# jamma-streamer.net
KiCad netlist of a schematic drawn in EAGLE
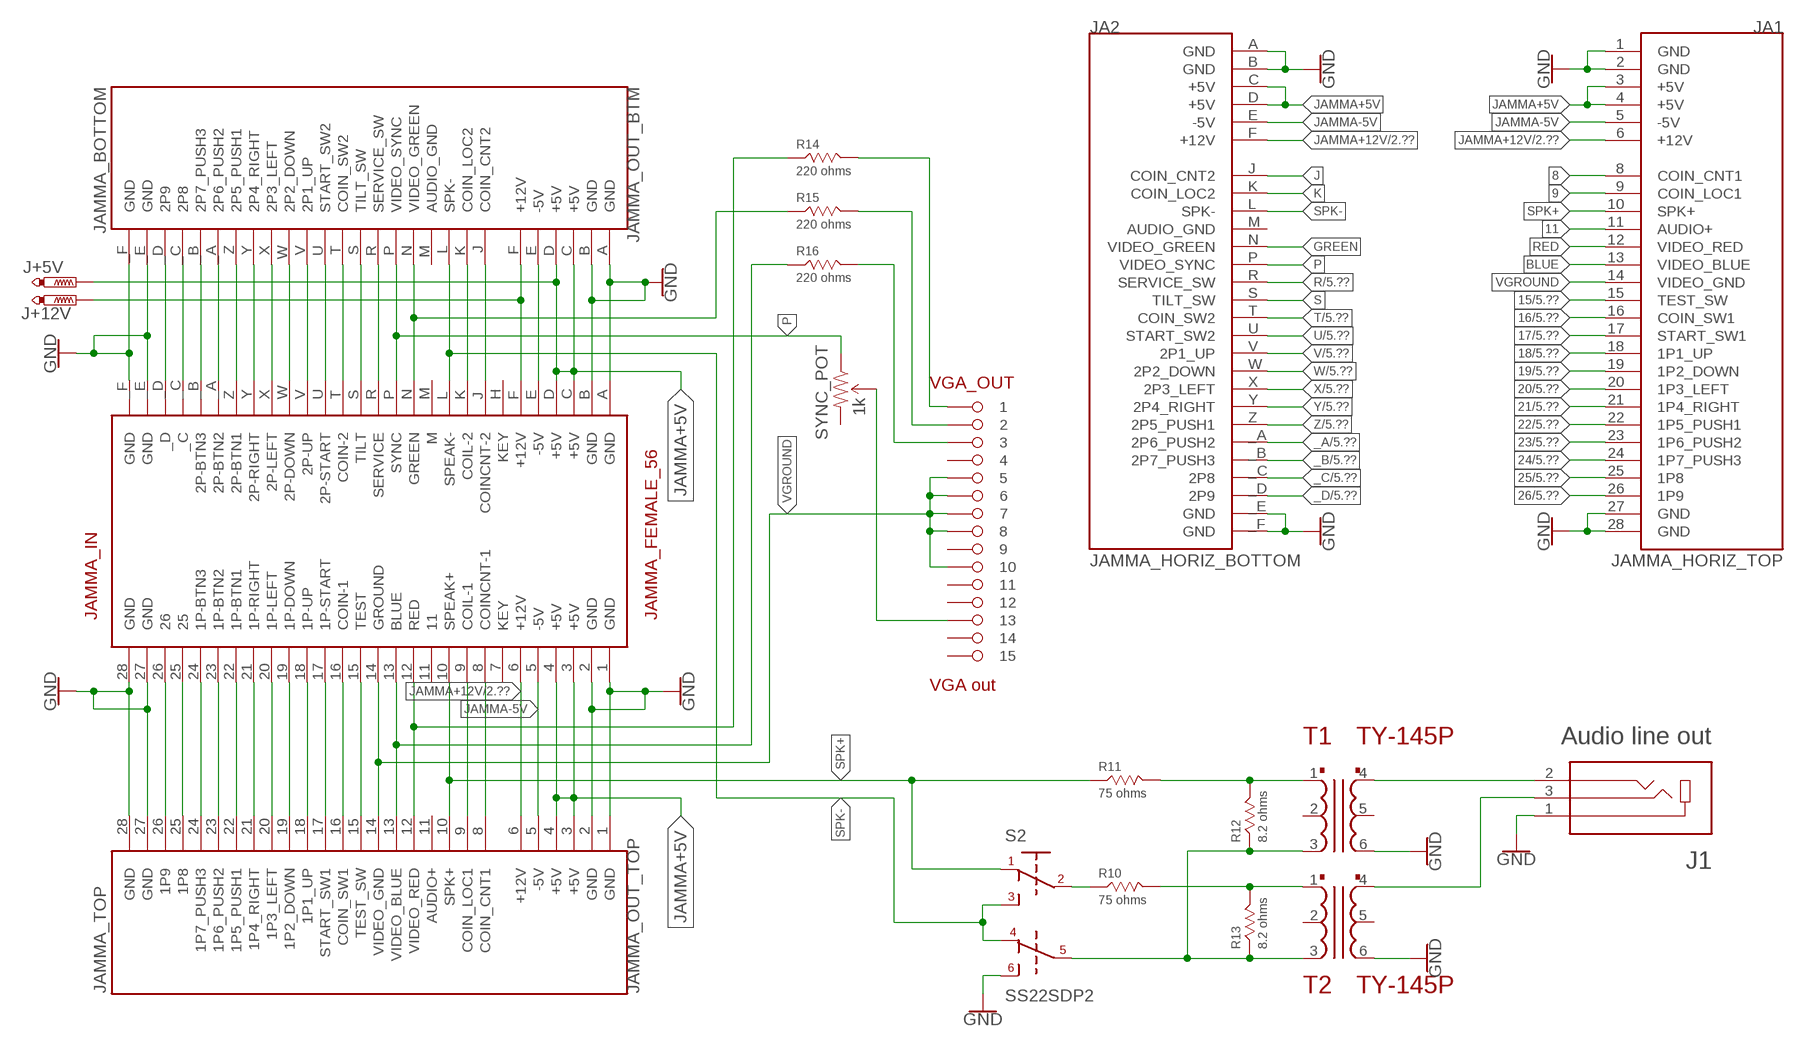
[diagram p0: schematic, sheet 1]
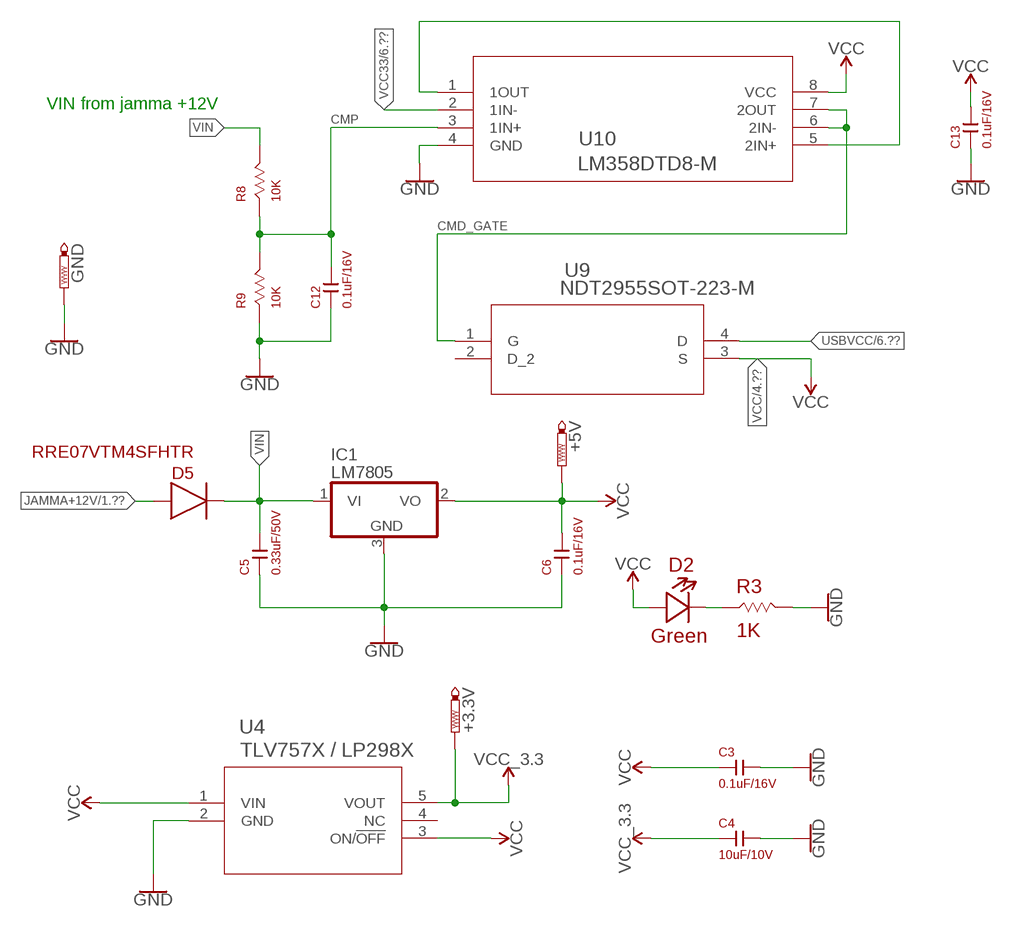
[diagram p1: schematic, sheet 2]
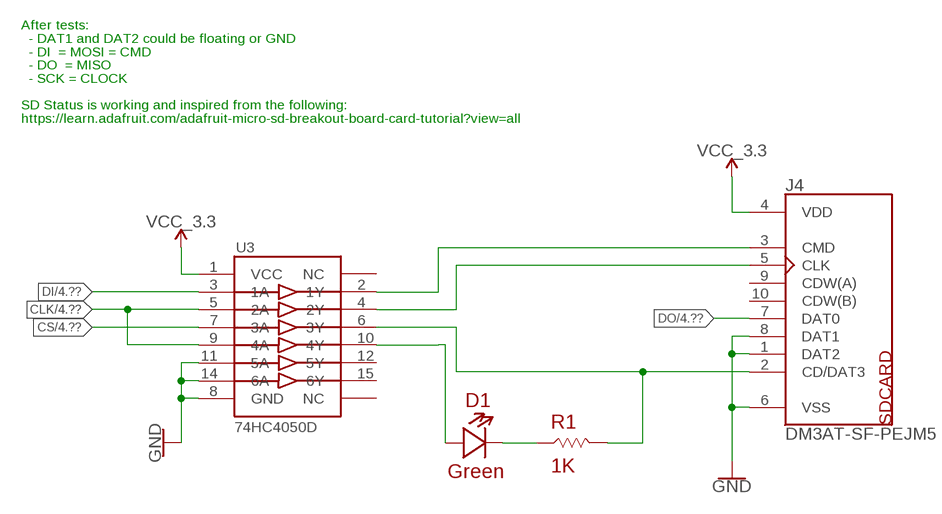
[diagram p2: schematic, sheet 3]
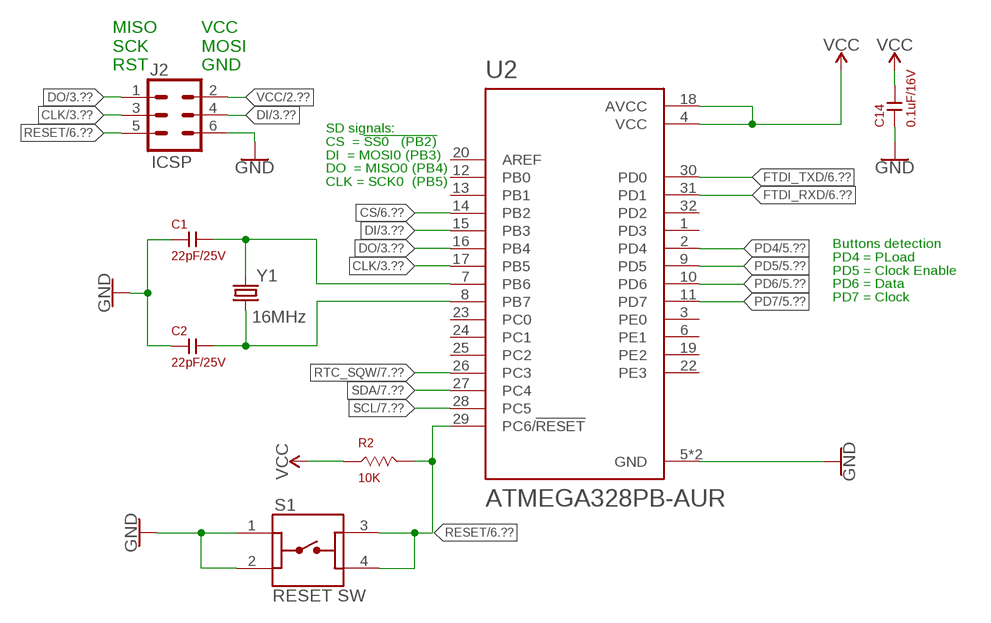
[diagram p3: schematic, sheet 4]
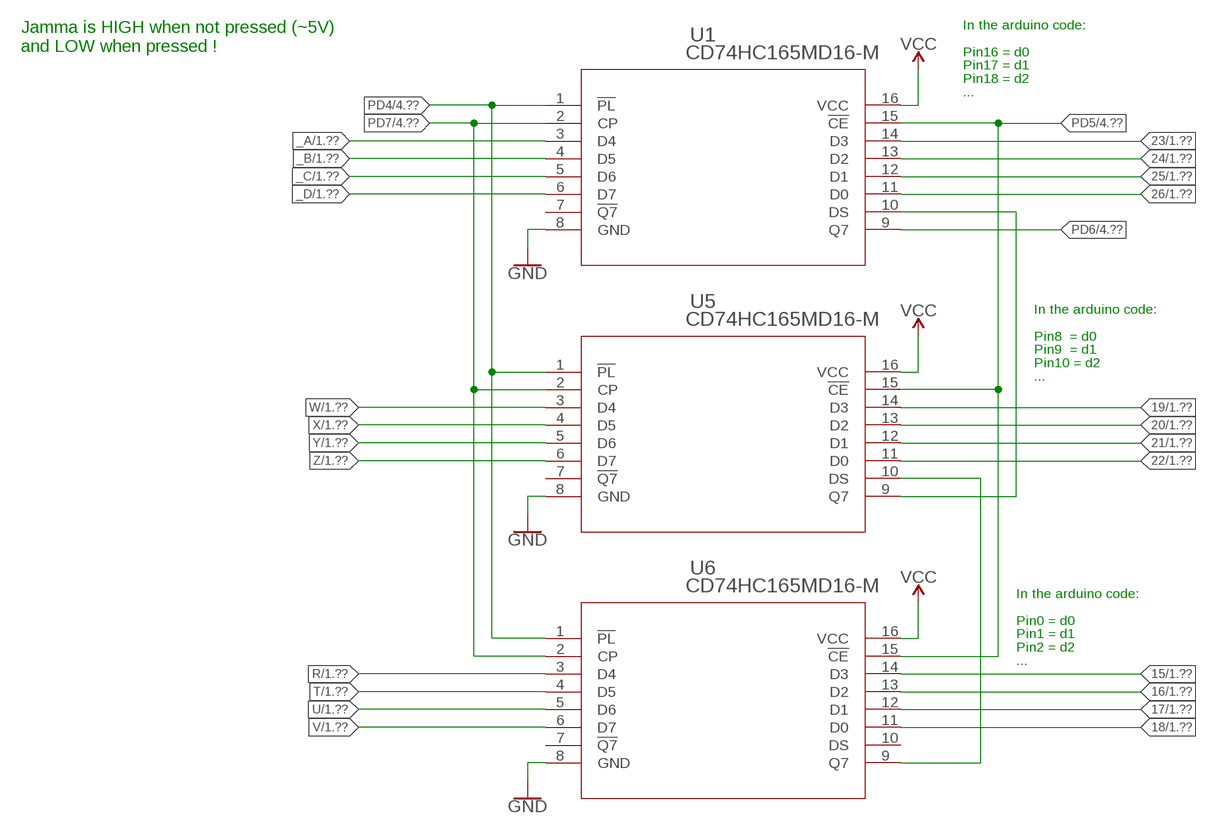
[diagram p4: schematic, sheet 5]
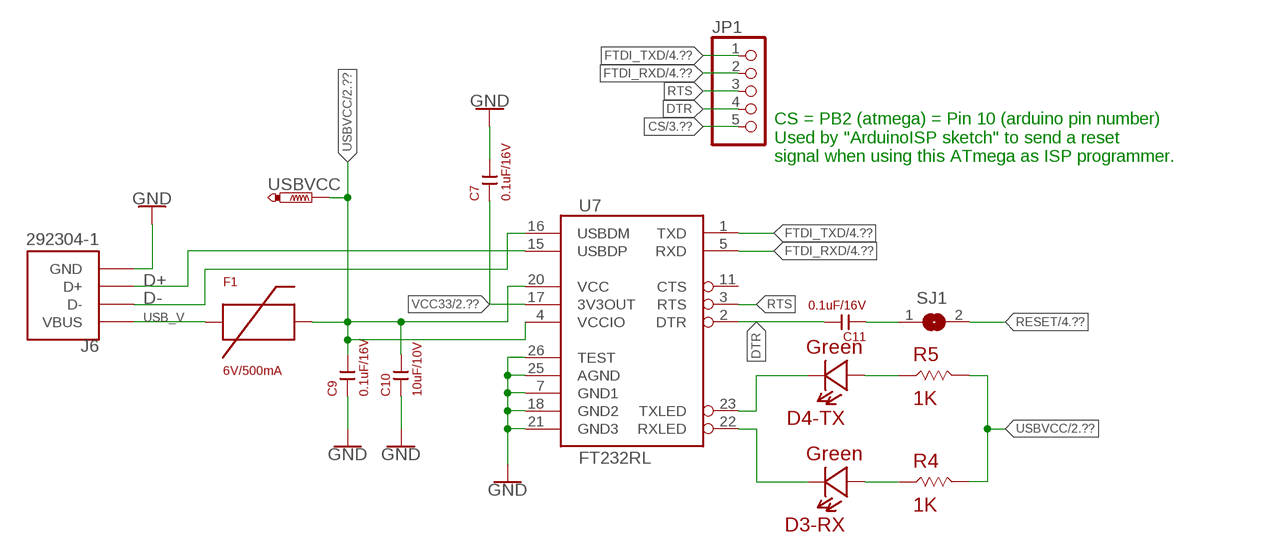
[diagram p5: schematic, sheet 6]
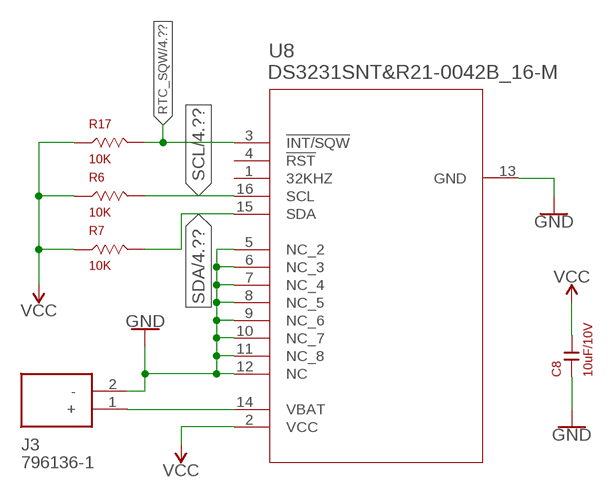
[diagram p6: schematic, sheet 7]

(export (version "E")
  (design (tool "Eeschema 10.0.6"))
  (components
    (comp (ref "U1")
      (value "CD74HC165MD16-M")
      (footprint "eagle-import:D16-M")
      (fields (field (name "MANUFACTURER_PART_NUMBER") "CD74HC165M"))
      (libsource (lib "eagle-import") (part "CD74HC165MD16-M"))
    )
    (comp (ref "U5")
      (value "CD74HC165MD16-M")
      (footprint "eagle-import:D16-M")
      (fields (field (name "MANUFACTURER_PART_NUMBER") "CD74HC165M"))
      (libsource (lib "eagle-import") (part "CD74HC165MD16-M"))
    )
    (comp (ref "U6")
      (value "CD74HC165MD16-M")
      (footprint "eagle-import:D16-M")
      (fields (field (name "MANUFACTURER_PART_NUMBER") "CD74HC165M"))
      (libsource (lib "eagle-import") (part "CD74HC165MD16-M"))
    )
    (comp (ref "D1")
      (value "Green")
      (footprint "eagle-import:604-APTD1608LCGCK")
      (libsource (lib "eagle-import") (part "604-APTD1608LCGCK"))
    )
    (comp (ref "J4")
      (value "DM3AT-SF-PEJM5")
      (footprint "eagle-import:DM3AT-SF-PEJM5_1")
      (fields (field (name "MOUSER_PART_NUMBER") "798-DM3AT-SF-PEJM5"))
      (libsource (lib "eagle-import") (part "DM3AT-SF-PEJM5"))
    )
    (comp (ref "R1")
      (value "1K")
      (footprint "eagle-import:652-CHP0603FX1001ELF")
      (libsource (lib "eagle-import") (part "BOURNS-652CHP0603FX1001ELF"))
    )
    (comp (ref "U3")
      (value "74HC4050D")
      (footprint "eagle-import:SO16")
      (fields (field (name "MF") "Toshiba Semiconductor"))
      (libsource (lib "eagle-import") (part "74HC4050D"))
    )
    (comp (ref "+3.3V")
      (value "PTR1TP15SQ")
      (footprint "eagle-import:TP15SQ")
      (libsource (lib "eagle-import") (part "PTR1TP15SQ"))
    )
    (comp (ref "+5V")
      (value "PTR1TP15SQ")
      (footprint "eagle-import:TP15SQ")
      (libsource (lib "eagle-import") (part "PTR1TP15SQ"))
    )
    (comp (ref "C3")
      (value "0.1uF/16V")
      (footprint "eagle-import:KEMET-C1210C104K4J")
      (libsource (lib "eagle-import") (part "KEMET-C1210C104K4J"))
    )
    (comp (ref "C4")
      (value "10uF/10V")
      (footprint "eagle-import:KEMET-C1210C106K8N")
      (libsource (lib "eagle-import") (part "KEMET-C1210C106K8N"))
    )
    (comp (ref "C5")
      (value "0.33uF/50V")
      (footprint "eagle-import:KEMET-C1206X334K5R")
      (libsource (lib "eagle-import") (part "KEMET-C1206X334K5R"))
    )
    (comp (ref "C6")
      (value "0.1uF/16V")
      (footprint "eagle-import:KEMET-C1210C104K4J")
      (libsource (lib "eagle-import") (part "KEMET-C1210C104K4J"))
    )
    (comp (ref "C12")
      (value "0.1uF/16V")
      (footprint "eagle-import:KEMET-C1210C104K4J")
      (libsource (lib "eagle-import") (part "KEMET-C1210C104K4J"))
    )
    (comp (ref "C13")
      (value "0.1uF/16V")
      (footprint "eagle-import:KEMET-C1210C104K4J")
      (libsource (lib "eagle-import") (part "KEMET-C1210C104K4J"))
    )
    (comp (ref "D2")
      (value "Green")
      (footprint "eagle-import:604-APTD1608LCGCK")
      (libsource (lib "eagle-import") (part "604-APTD1608LCGCK"))
    )
    (comp (ref "D5")
      (value "RRE07VTM4SFHTR")
      (footprint "eagle-import:DIODE-RRE07VTM4SFHTR")
      (libsource (lib "eagle-import") (part "RRE07VTM4SFHTR"))
    )
    (comp (ref "GND")
      (value "PTR1TP15SQ")
      (footprint "eagle-import:TP15SQ")
      (libsource (lib "eagle-import") (part "PTR1TP15SQ"))
    )
    (comp (ref "IC1")
      (value "LM7805")
      (footprint "eagle-import:TO252")
      (libsource (lib "eagle-import") (part "78DT05"))
    )
    (comp (ref "R3")
      (value "1K")
      (footprint "eagle-import:652-CHP0603FX1001ELF")
      (libsource (lib "eagle-import") (part "BOURNS-652CHP0603FX1001ELF"))
    )
    (comp (ref "R8")
      (value "10K")
      (footprint "eagle-import:BOURNS-CRM2512AJW-103ELF")
      (libsource (lib "eagle-import") (part "BOURNS-CRM2512AJW103ELF"))
    )
    (comp (ref "R9")
      (value "10K")
      (footprint "eagle-import:BOURNS-CRM2512AJW-103ELF")
      (libsource (lib "eagle-import") (part "BOURNS-CRM2512AJW103ELF"))
    )
    (comp (ref "U4")
      (value "TLV757X / LP298X")
      (footprint "eagle-import:DBV5-M")
      (fields (field (name "MANUFACTURER_PART_NUMBER") "LP298133DBVR"))
      (libsource (lib "eagle-import") (part "LP2981-33DBVRDBV5-M"))
    )
    (comp (ref "U9")
      (value "NDT2955SOT-223-M")
      (footprint "eagle-import:SOT-223-M")
      (fields (field (name "MANUFACTURER_PART_NUMBER") "NDT2955"))
      (libsource (lib "eagle-import") (part "NDT2955SOT-223-M"))
    )
    (comp (ref "U10")
      (value "LM358DTD8-M")
      (footprint "eagle-import:D8-M")
      (fields (field (name "MANUFACTURER_PART_NUMBER") "LM358DT"))
      (libsource (lib "eagle-import") (part "LM358DTD8-M"))
    )
    (comp (ref "J+5V")
      (value "PTR1TP15SQ")
      (footprint "eagle-import:TP15SQ")
      (libsource (lib "eagle-import") (part "PTR1TP15SQ"))
    )
    (comp (ref "J+12V")
      (value "PTR1TP15SQ")
      (footprint "eagle-import:TP15SQ")
      (libsource (lib "eagle-import") (part "PTR1TP15SQ"))
    )
    (comp (ref "J1")
      (value "Audio line out")
      (footprint "eagle-import:CUI_SJ1-3523N")
      (fields
        (field (name "DIGI-KEY_PART_NUMBER") "CP1-3523N-ND")
        (field (name "MF") "CUI Inc.")
        (field (name "MP") "SJ1-3523N")
        (field (name "SPICEPREFIX") "J")
      )
      (libsource (lib "eagle-import") (part "SJ1-3523N"))
    )
    (comp (ref "JA1")
      (value "JAMMA_HORIZ_TOP")
      (footprint "eagle-import:JAMMA_HORIZ_TOP")
      (libsource (lib "eagle-import") (part "JAMMA_HORIZ_TOP"))
    )
    (comp (ref "JA2")
      (value "JAMMA_HORIZ_BOTTOM")
      (footprint "eagle-import:JAMMA_HORIZ_BOTTOM")
      (libsource (lib "eagle-import") (part "JAMMA_HORIZ_BOTTOM"))
    )
    (comp (ref "JAMMA_IN")
      (value "JAMMA_FEMALE_56")
      (footprint "eagle-import:JAMMA_FEMALE_56")
      (libsource (lib "eagle-import") (part "JAMMA_FEMALE_56"))
    )
    (comp (ref "JAMMA_OUT_BTM")
      (value "JAMMA_BOTTOM")
      (footprint "eagle-import:JAMMA_BOTTOM")
      (libsource (lib "eagle-import") (part "JAMMA_BOTTOM"))
    )
    (comp (ref "JAMMA_OUT_TOP")
      (value "JAMMA_TOP")
      (footprint "eagle-import:JAMMA_TOP")
      (libsource (lib "eagle-import") (part "JAMMA_TOP"))
    )
    (comp (ref "R10")
      (value "75 ohms")
      (footprint "eagle-import:TE_3550_SERIES")
      (fields (field (name "POWER") "5W") (field (name "MOUSER_REF") "279-355075RFT"))
      (libsource (lib "eagle-import") (part "TE3550"))
    )
    (comp (ref "R11")
      (value "75 ohms")
      (footprint "eagle-import:TE_3550_SERIES")
      (fields (field (name "POWER") "5W") (field (name "MOUSER_REF") "279-355075RFT"))
      (libsource (lib "eagle-import") (part "TE3550"))
    )
    (comp (ref "R12")
      (value "8.2 ohms")
      (footprint "eagle-import:TE_3550_SERIES")
      (fields (field (name "POWER") "5W") (field (name "MOUSER_REF") "279-35508R2JT"))
      (libsource (lib "eagle-import") (part "TE3550"))
    )
    (comp (ref "R13")
      (value "8.2 ohms")
      (footprint "eagle-import:TE_3550_SERIES")
      (fields (field (name "POWER") "5W") (field (name "MOUSER_REF") "279-35508R2JT"))
      (libsource (lib "eagle-import") (part "TE3550"))
    )
    (comp (ref "R14")
      (value "220 ohms")
      (footprint "eagle-import:RESC3225X70N")
      (fields
        (field (name "MANUFACTURER_PART_NUMBER") "ERJ-14NF2200U")
        (field (name "MOUSER_PART_NUMBER") "667-ERJ-14NF2200U")
      )
      (libsource (lib "eagle-import") (part "ERJ-14NF2200U"))
    )
    (comp (ref "R15")
      (value "220 ohms")
      (footprint "eagle-import:RESC3225X70N")
      (fields
        (field (name "MANUFACTURER_PART_NUMBER") "ERJ-14NF2200U")
        (field (name "MOUSER_PART_NUMBER") "667-ERJ-14NF2200U")
      )
      (libsource (lib "eagle-import") (part "ERJ-14NF2200U"))
    )
    (comp (ref "R16")
      (value "220 ohms")
      (footprint "eagle-import:RESC3225X70N")
      (fields
        (field (name "MANUFACTURER_PART_NUMBER") "ERJ-14NF2200U")
        (field (name "MOUSER_PART_NUMBER") "667-ERJ-14NF2200U")
      )
      (libsource (lib "eagle-import") (part "ERJ-14NF2200U"))
    )
    (comp (ref "S2")
      (value "SS22SDP2")
      (footprint "eagle-import:SS22SDP2(DPDT)")
      (fields (field (name "MOUSER_PART_NUMBER") "633-SS22SDP2") (field (name "SPICEPREFIX") "X"))
      (libsource (lib "eagle-import") (part "SS22SDP2"))
    )
    (comp (ref "SYNC_POT")
      (value "1k")
      (footprint "eagle-import:TRIM_POT_PTH")
      (libsource (lib "eagle-import") (part "TRIMPOTPTH"))
    )
    (comp (ref "T1")
      (value "TY-145P")
      (footprint "eagle-import:TRIAD-TY-145P")
      (fields (field (name "SPICEPREFIX") "X"))
      (libsource (lib "eagle-import") (part "TRIAD-TY-145P"))
    )
    (comp (ref "T2")
      (value "TY-145P")
      (footprint "eagle-import:TRIAD-TY-145P")
      (fields (field (name "SPICEPREFIX") "X"))
      (libsource (lib "eagle-import") (part "TRIAD-TY-145P"))
    )
    (comp (ref "VGA_OUT")
      (value "VGA out")
      (footprint "eagle-import:HARTING-DSUB-15-FEMALE")
      (libsource (lib "eagle-import") (part "HARTING-DSUB-15-FEMALE"))
    )
    (comp (ref "C7")
      (value "0.1uF/16V")
      (footprint "eagle-import:KEMET-C1210C104K4J")
      (libsource (lib "eagle-import") (part "KEMET-C1210C104K4J"))
    )
    (comp (ref "C9")
      (value "0.1uF/16V")
      (footprint "eagle-import:KEMET-C1210C104K4J")
      (libsource (lib "eagle-import") (part "KEMET-C1210C104K4J"))
    )
    (comp (ref "C10")
      (value "10uF/10V")
      (footprint "eagle-import:KEMET-C1210C106K8N")
      (libsource (lib "eagle-import") (part "KEMET-C1210C106K8N"))
    )
    (comp (ref "C11")
      (value "0.1uF/16V")
      (footprint "eagle-import:KEMET-C1210C104K4J")
      (libsource (lib "eagle-import") (part "KEMET-C1210C104K4J"))
    )
    (comp (ref "D3-RX")
      (value "Green")
      (footprint "eagle-import:604-APTD1608LCGCK")
      (libsource (lib "eagle-import") (part "604-APTD1608LCGCK"))
    )
    (comp (ref "D4-TX")
      (value "Green")
      (footprint "eagle-import:604-APTD1608LCGCK")
      (libsource (lib "eagle-import") (part "604-APTD1608LCGCK"))
    )
    (comp (ref "F1")
      (value "6V/500mA")
      (footprint "eagle-import:FUSE-1206L050YR")
      (libsource (lib "eagle-import") (part "1206L050YRSMD"))
    )
    (comp (ref "J6")
      (value "292304-1")
      (footprint "eagle-import:TE_292304-1")
      (fields (field (name "DIGI-KEY_PART_NUMBER") "A31725-ND") (field (name "MF") "TE Connectivity"))
      (libsource (lib "eagle-import") (part "292304-1"))
    )
    (comp (ref "JP1")
      (value "PINHD-1X5")
      (footprint "eagle-import:1X05")
      (libsource (lib "eagle-import") (part "PINHD-1X5"))
    )
    (comp (ref "R4")
      (value "1K")
      (footprint "eagle-import:652-CHP0603FX1001ELF")
      (libsource (lib "eagle-import") (part "BOURNS-652CHP0603FX1001ELF"))
    )
    (comp (ref "R5")
      (value "1K")
      (footprint "eagle-import:652-CHP0603FX1001ELF")
      (libsource (lib "eagle-import") (part "BOURNS-652CHP0603FX1001ELF"))
    )
    (comp (ref "SJ1") (value "SJ") (footprint "eagle-import:SJ") (libsource (lib "eagle-import") (part "SJ")))
    (comp (ref "U7")
      (value "FT232RL")
      (footprint "eagle-import:SSOP28DB")
      (libsource (lib "eagle-import") (part "FT232RL-BASICSSOP"))
    )
    (comp (ref "USBVCC")
      (value "PTR1TP15SQ")
      (footprint "eagle-import:TP15SQ")
      (libsource (lib "eagle-import") (part "PTR1TP15SQ"))
    )
    (comp (ref "C8")
      (value "10uF/10V")
      (footprint "eagle-import:KEMET-C1210C106K8N")
      (libsource (lib "eagle-import") (part "KEMET-C1210C106K8N"))
    )
    (comp (ref "J3")
      (value "796136-1")
      (footprint "eagle-import:796136-1")
      (fields (field (name "MOUSER_PART_NUMBER") "571-796136-1"))
      (libsource (lib "eagle-import") (part "796136-1"))
    )
    (comp (ref "R6")
      (value "10K")
      (footprint "eagle-import:BOURNS-CRM2512AJW-103ELF")
      (libsource (lib "eagle-import") (part "BOURNS-CRM2512AJW103ELF"))
    )
    (comp (ref "R7")
      (value "10K")
      (footprint "eagle-import:BOURNS-CRM2512AJW-103ELF")
      (libsource (lib "eagle-import") (part "BOURNS-CRM2512AJW103ELF"))
    )
    (comp (ref "R17")
      (value "10K")
      (footprint "eagle-import:BOURNS-CRM2512AJW-103ELF")
      (libsource (lib "eagle-import") (part "BOURNS-CRM2512AJW103ELF"))
    )
    (comp (ref "U8")
      (value "DS3231SNT&R21-0042B_16-M")
      (footprint "eagle-import:21-0042B_16-M")
      (fields (field (name "MANUFACTURER_PART_NUMBER") "DS3231SN#T&R"))
      (libsource (lib "eagle-import") (part "DS3231SNT&R21-0042B_16-M"))
    )
    (comp (ref "C1")
      (value "22pF/25V")
      (footprint "eagle-import:KEMET-C1206C220K3HACTU")
      (libsource (lib "eagle-import") (part "KEMET-C1206C220K3HACTU"))
    )
    (comp (ref "C2")
      (value "22pF/25V")
      (footprint "eagle-import:KEMET-C1206C220K3HACTU")
      (libsource (lib "eagle-import") (part "KEMET-C1206C220K3HACTU"))
    )
    (comp (ref "C14")
      (value "0.1uF/16V")
      (footprint "eagle-import:KEMET-C1210C104K4J")
      (libsource (lib "eagle-import") (part "KEMET-C1210C104K4J"))
    )
    (comp (ref "J2")
      (value "ICSP")
      (footprint "eagle-import:2X3")
      (libsource (lib "eagle-import") (part "CONN_03X22X3_SILK_MALE_PTH"))
    )
    (comp (ref "R2")
      (value "10K")
      (footprint "eagle-import:BOURNS-CRM2512AJW-103ELF")
      (libsource (lib "eagle-import") (part "BOURNS-CRM2512AJW103ELF"))
    )
    (comp (ref "S1")
      (value "RESET SW")
      (footprint "eagle-import:SW_1825910-7")
      (fields
        (field (name "COMMENT") "1825910-7")
        (field (name "DIGI-KEY_PART_NUMBER") "450-1804-ND")
        (field (name "MF") "TE Connectivity")
      )
      (libsource (lib "eagle-import") (part "1825910-7"))
    )
    (comp (ref "U2")
      (value "ATMEGA328PB-AUR")
      (footprint "eagle-import:QFP80P900X900X120-32N")
      (fields (field (name "MF") "Microchip"))
      (libsource (lib "eagle-import") (part "ATMEGA328PB-AUR"))
    )
    (comp (ref "Y1")
      (value "16MHz")
      (footprint "eagle-import:HC49US")
      (libsource (lib "eagle-import") (part "CRYSTAL-16MHZPTH-HC49US"))
    )
  )
  (nets
    (net (code "1") (name "8") (class "Default")
      (node (ref "JA1") (pin "8") (pinfunction "COIN_CNT1_8") (pintype "bidirectional"))
      (node (ref "JAMMA_IN") (pin "8") (pinfunction "COINCNT-1_8") (pintype "bidirectional"))
      (node (ref "JAMMA_OUT_TOP") (pin "8") (pinfunction "COIN_CNT1_8") (pintype "bidirectional"))
    )
    (net (code "2") (name "9") (class "Default")
      (node (ref "JA1") (pin "9") (pinfunction "COIN_LOC1_9") (pintype "bidirectional"))
      (node (ref "JAMMA_IN") (pin "9") (pinfunction "COIL-1_9") (pintype "bidirectional"))
      (node (ref "JAMMA_OUT_TOP") (pin "9") (pinfunction "COIN_LOC1_9") (pintype "bidirectional"))
    )
    (net (code "3") (name "11") (class "Default")
      (node (ref "JA1") (pin "11") (pinfunction "AUDIO+_11") (pintype "output"))
    )
    (net (code "4") (name "15") (class "Default")
      (node (ref "JA1") (pin "15") (pinfunction "TEST_SW_15") (pintype "input"))
      (node (ref "JAMMA_IN") (pin "15") (pinfunction "TEST_15") (pintype "output"))
      (node (ref "JAMMA_OUT_TOP") (pin "15") (pinfunction "TEST_SW_15") (pintype "input"))
      (node (ref "U6") (pin "14") (pinfunction "D3_14") (pintype "input"))
    )
    (net (code "5") (name "16") (class "Default")
      (node (ref "JA1") (pin "16") (pinfunction "COIN_SW1_16") (pintype "input"))
      (node (ref "JAMMA_IN") (pin "16") (pinfunction "COIN-1_16") (pintype "output"))
      (node (ref "JAMMA_OUT_TOP") (pin "16") (pinfunction "COIN_SW1_16") (pintype "input"))
      (node (ref "U6") (pin "13") (pinfunction "D2_13") (pintype "input"))
    )
    (net (code "6") (name "17") (class "Default")
      (node (ref "JA1") (pin "17") (pinfunction "START_SW1_17") (pintype "input"))
      (node (ref "JAMMA_IN") (pin "17") (pinfunction "1P-START_17") (pintype "output"))
      (node (ref "JAMMA_OUT_TOP") (pin "17") (pinfunction "START_SW1_17") (pintype "input"))
      (node (ref "U6") (pin "12") (pinfunction "D1_12") (pintype "input"))
    )
    (net (code "7") (name "18") (class "Default")
      (node (ref "JA1") (pin "18") (pinfunction "1P1_UP_18") (pintype "input"))
      (node (ref "JAMMA_IN") (pin "18") (pinfunction "1P-UP_18") (pintype "output"))
      (node (ref "JAMMA_OUT_TOP") (pin "18") (pinfunction "1P1_UP_18") (pintype "input"))
      (node (ref "U6") (pin "11") (pinfunction "D0_11") (pintype "input"))
    )
    (net (code "8") (name "19") (class "Default")
      (node (ref "JA1") (pin "19") (pinfunction "1P2_DOWN_19") (pintype "input"))
      (node (ref "JAMMA_IN") (pin "19") (pinfunction "1P-DOWN_19") (pintype "output"))
      (node (ref "JAMMA_OUT_TOP") (pin "19") (pinfunction "1P2_DOWN_19") (pintype "input"))
      (node (ref "U5") (pin "14") (pinfunction "D3_14") (pintype "input"))
    )
    (net (code "9") (name "20") (class "Default")
      (node (ref "JA1") (pin "20") (pinfunction "1P3_LEFT_20") (pintype "input"))
      (node (ref "JAMMA_IN") (pin "20") (pinfunction "1P-LEFT_20") (pintype "output"))
      (node (ref "JAMMA_OUT_TOP") (pin "20") (pinfunction "1P3_LEFT_20") (pintype "input"))
      (node (ref "U5") (pin "13") (pinfunction "D2_13") (pintype "input"))
    )
    (net (code "10") (name "21") (class "Default")
      (node (ref "JA1") (pin "21") (pinfunction "1P4_RIGHT_21") (pintype "input"))
      (node (ref "JAMMA_IN") (pin "21") (pinfunction "1P-RIGHT_21") (pintype "output"))
      (node (ref "JAMMA_OUT_TOP") (pin "21") (pinfunction "1P4_RIGHT_21") (pintype "input"))
      (node (ref "U5") (pin "12") (pinfunction "D1_12") (pintype "input"))
    )
    (net (code "11") (name "22") (class "Default")
      (node (ref "JA1") (pin "22") (pinfunction "1P5_PUSH1_22") (pintype "input"))
      (node (ref "JAMMA_IN") (pin "22") (pinfunction "1P-BTN1_22") (pintype "output"))
      (node (ref "JAMMA_OUT_TOP") (pin "22") (pinfunction "1P5_PUSH1_22") (pintype "input"))
      (node (ref "U5") (pin "11") (pinfunction "D0_11") (pintype "input"))
    )
    (net (code "12") (name "23") (class "Default")
      (node (ref "JA1") (pin "23") (pinfunction "1P6_PUSH2_23") (pintype "input"))
      (node (ref "JAMMA_IN") (pin "23") (pinfunction "1P-BTN2_23") (pintype "output"))
      (node (ref "JAMMA_OUT_TOP") (pin "23") (pinfunction "1P6_PUSH2_23") (pintype "input"))
      (node (ref "U1") (pin "14") (pinfunction "D3_14") (pintype "input"))
    )
    (net (code "13") (name "24") (class "Default")
      (node (ref "JA1") (pin "24") (pinfunction "1P7_PUSH3_24") (pintype "input"))
      (node (ref "JAMMA_IN") (pin "24") (pinfunction "1P-BTN3_24") (pintype "output"))
      (node (ref "JAMMA_OUT_TOP") (pin "24") (pinfunction "1P7_PUSH3_24") (pintype "input"))
      (node (ref "U1") (pin "13") (pinfunction "D2_13") (pintype "input"))
    )
    (net (code "14") (name "25") (class "Default")
      (node (ref "JA1") (pin "25") (pinfunction "1P8_25") (pintype "input"))
      (node (ref "JAMMA_IN") (pin "25") (pinfunction "25_25") (pintype "output"))
      (node (ref "JAMMA_OUT_TOP") (pin "25") (pinfunction "1P8_25") (pintype "input"))
      (node (ref "U1") (pin "12") (pinfunction "D1_12") (pintype "input"))
    )
    (net (code "15") (name "26") (class "Default")
      (node (ref "JA1") (pin "26") (pinfunction "1P9_26") (pintype "input"))
      (node (ref "JAMMA_IN") (pin "26") (pinfunction "26_26") (pintype "output"))
      (node (ref "JAMMA_OUT_TOP") (pin "26") (pinfunction "1P9_26") (pintype "input"))
      (node (ref "U1") (pin "11") (pinfunction "D0_11") (pintype "input"))
    )
    (net (code "16") (name "BLUE") (class "Default")
      (node (ref "JA1") (pin "13") (pinfunction "VIDEO_BLUE_13") (pintype "output"))
      (node (ref "JAMMA_IN") (pin "13") (pinfunction "BLUE_13") (pintype "input"))
      (node (ref "JAMMA_OUT_TOP") (pin "13") (pinfunction "VIDEO_BLUE_13") (pintype "output"))
      (node (ref "R16") (pin "1") (pinfunction "P$1_1") (pintype "passive"))
    )
    (net (code "17") (name "CLK") (class "Default")
      (node (ref "J2") (pin "3") (pinfunction "3_3") (pintype "bidirectional"))
      (node (ref "U2") (pin "17") (pinfunction "PB5_17") (pintype "bidirectional"))
      (node (ref "U3") (pin "5") (pinfunction "2A_5") (pintype "input"))
      (node (ref "U3") (pin "9") (pinfunction "4A_9") (pintype "input"))
    )
    (net (code "18") (name "CMD_GATE") (class "Default")
      (node (ref "U10") (pin "6") (pinfunction "2IN-_6") (pintype "input"))
      (node (ref "U10") (pin "7") (pinfunction "2OUT_7") (pintype "output"))
      (node (ref "U9") (pin "1") (pinfunction "G_1") (pintype "passive"))
    )
    (net (code "19") (name "CMP") (class "Default")
      (node (ref "C12") (pin "1") (pinfunction "P$1_1") (pintype "passive"))
      (node (ref "R8") (pin "1") (pinfunction "P$1_1") (pintype "passive"))
      (node (ref "R9") (pin "2") (pinfunction "P$2_2") (pintype "passive"))
      (node (ref "U10") (pin "3") (pinfunction "1IN+_3") (pintype "input"))
    )
    (net (code "20") (name "CS") (class "Default")
      (node (ref "JP1") (pin "5") (pinfunction "5_5") (pintype "passive"))
      (node (ref "U2") (pin "14") (pinfunction "PB2_14") (pintype "bidirectional"))
      (node (ref "U3") (pin "7") (pinfunction "3A_7") (pintype "input"))
    )
    (net (code "21") (name "D+") (class "Default")
      (node (ref "J6") (pin "3") (pinfunction "D+_3") (pintype "bidirectional"))
      (node (ref "U7") (pin "15") (pinfunction "USBDP_15") (pintype "bidirectional"))
    )
    (net (code "22") (name "D-") (class "Default")
      (node (ref "J6") (pin "2") (pinfunction "D-_2") (pintype "bidirectional"))
      (node (ref "U7") (pin "16") (pinfunction "USBDM_16") (pintype "bidirectional"))
    )
    (net (code "23") (name "DI") (class "Default")
      (node (ref "J2") (pin "4") (pinfunction "4_4") (pintype "bidirectional"))
      (node (ref "U2") (pin "15") (pinfunction "PB3_15") (pintype "bidirectional"))
      (node (ref "U3") (pin "3") (pinfunction "1A_3") (pintype "input"))
    )
    (net (code "24") (name "DO") (class "Default")
      (node (ref "J2") (pin "1") (pinfunction "1_1") (pintype "bidirectional"))
      (node (ref "J4") (pin "7") (pinfunction "DAT0_7") (pintype "bidirectional"))
      (node (ref "U2") (pin "16") (pinfunction "PB4_16") (pintype "bidirectional"))
    )
    (net (code "25") (name "DTR") (class "Default")
      (node (ref "C11") (pin "1") (pinfunction "P$1_1") (pintype "passive"))
      (node (ref "JP1") (pin "4") (pinfunction "4_4") (pintype "passive"))
      (node (ref "U7") (pin "2") (pinfunction "DTR_2") (pintype "bidirectional"))
    )
    (net (code "26") (name "FTDI_RXD") (class "Default")
      (node (ref "JP1") (pin "2") (pinfunction "2_2") (pintype "passive"))
      (node (ref "U2") (pin "31") (pinfunction "PD1_31") (pintype "bidirectional"))
      (node (ref "U7") (pin "5") (pinfunction "RXD_5") (pintype "input"))
    )
    (net (code "27") (name "FTDI_TXD") (class "Default")
      (node (ref "JP1") (pin "1") (pinfunction "1_1") (pintype "passive"))
      (node (ref "U2") (pin "30") (pinfunction "PD0_30") (pintype "bidirectional"))
      (node (ref "U7") (pin "1") (pinfunction "TXD_1") (pintype "output"))
    )
    (net (code "28") (name "GND") (class "Default")
      (node (ref "C1") (pin "2") (pinfunction "P$2_2") (pintype "passive"))
      (node (ref "C10") (pin "2") (pinfunction "P$2_2") (pintype "passive"))
      (node (ref "C12") (pin "2") (pinfunction "P$2_2") (pintype "passive"))
      (node (ref "C13") (pin "2") (pinfunction "P$2_2") (pintype "passive"))
      (node (ref "C14") (pin "2") (pinfunction "P$2_2") (pintype "passive"))
      (node (ref "C2") (pin "2") (pinfunction "P$2_2") (pintype "passive"))
      (node (ref "C3") (pin "1") (pinfunction "P$1_1") (pintype "passive"))
      (node (ref "C4") (pin "1") (pinfunction "P$1_1") (pintype "passive"))
      (node (ref "C5") (pin "2") (pinfunction "P$2_2") (pintype "passive"))
      (node (ref "C6") (pin "2") (pinfunction "P$2_2") (pintype "passive"))
      (node (ref "C7") (pin "1") (pinfunction "P$1_1") (pintype "passive"))
      (node (ref "C8") (pin "2") (pinfunction "P$2_2") (pintype "passive"))
      (node (ref "C9") (pin "2") (pinfunction "P$2_2") (pintype "passive"))
      (node (ref "GND") (pin "TP") (pinfunction "TP_TP") (pintype "input"))
      (node (ref "IC1") (pin "3") (pinfunction "GND_3") (pintype "passive"))
      (node (ref "J1") (pin "1") (pinfunction "1_1") (pintype "passive"))
      (node (ref "J2") (pin "6") (pinfunction "6_6") (pintype "bidirectional"))
      (node (ref "J3") (pin "2") (pinfunction "-_2") (pintype "bidirectional"))
      (node (ref "J4") (pin "1") (pinfunction "DAT2_1") (pintype "bidirectional"))
      (node (ref "J4") (pin "6") (pinfunction "VSS_6") (pintype "bidirectional"))
      (node (ref "J4") (pin "8") (pinfunction "DAT1_8") (pintype "bidirectional"))
      (node (ref "J6") (pin "4") (pinfunction "GND_4") (pintype "power_in"))
      (node (ref "JA1") (pin "1") (pinfunction "GND_1") (pintype "power_in"))
      (node (ref "JA1") (pin "2") (pinfunction "GND_2") (pintype "power_in"))
      (node (ref "JA1") (pin "27") (pinfunction "GND_27") (pintype "power_in"))
      (node (ref "JA1") (pin "28") (pinfunction "GND_28") (pintype "power_in"))
      (node (ref "JA2") (pin "A") (pinfunction "GND_A") (pintype "power_in"))
      (node (ref "JA2") (pin "B") (pinfunction "GND_B") (pintype "power_in"))
      (node (ref "JA2") (pin "_E") (pinfunction "GND__E") (pintype "power_in"))
      (node (ref "JA2") (pin "_F") (pinfunction "GND__F") (pintype "power_in"))
      (node (ref "JAMMA_IN") (pin "1") (pinfunction "GND_1") (pintype "power_in"))
      (node (ref "JAMMA_IN") (pin "2") (pinfunction "GND_2") (pintype "power_in"))
      (node (ref "JAMMA_IN") (pin "27") (pinfunction "GND_27") (pintype "power_in"))
      (node (ref "JAMMA_IN") (pin "28") (pinfunction "GND_28") (pintype "power_in"))
      (node (ref "JAMMA_IN") (pin "A") (pinfunction "GND_A") (pintype "power_in"))
      (node (ref "JAMMA_IN") (pin "B") (pinfunction "GND_B") (pintype "power_in"))
      (node (ref "JAMMA_IN") (pin "_E") (pinfunction "GND__E") (pintype "power_in"))
      (node (ref "JAMMA_IN") (pin "_F") (pinfunction "GND__F") (pintype "power_in"))
      (node (ref "JAMMA_OUT_BTM") (pin "A") (pinfunction "GND_A") (pintype "power_in"))
      (node (ref "JAMMA_OUT_BTM") (pin "B") (pinfunction "GND_B") (pintype "power_in"))
      (node (ref "JAMMA_OUT_BTM") (pin "_E") (pinfunction "GND__E") (pintype "power_in"))
      (node (ref "JAMMA_OUT_BTM") (pin "_F") (pinfunction "GND__F") (pintype "power_in"))
      (node (ref "JAMMA_OUT_TOP") (pin "1") (pinfunction "GND_1") (pintype "power_in"))
      (node (ref "JAMMA_OUT_TOP") (pin "2") (pinfunction "GND_2") (pintype "power_in"))
      (node (ref "JAMMA_OUT_TOP") (pin "27") (pinfunction "GND_27") (pintype "power_in"))
      (node (ref "JAMMA_OUT_TOP") (pin "28") (pinfunction "GND_28") (pintype "power_in"))
      (node (ref "R3") (pin "2") (pinfunction "P$2_2") (pintype "passive"))
      (node (ref "R9") (pin "1") (pinfunction "P$1_1") (pintype "passive"))
      (node (ref "S1") (pin "1") (pinfunction "1_1") (pintype "passive"))
      (node (ref "S1") (pin "2") (pinfunction "2_2") (pintype "passive"))
      (node (ref "S2") (pin "6") (pinfunction "6_6") (pintype "passive"))
      (node (ref "T1") (pin "6") (pinfunction "6_6") (pintype "passive"))
      (node (ref "T2") (pin "6") (pinfunction "6_6") (pintype "passive"))
      (node (ref "U1") (pin "8") (pinfunction "GND_8") (pintype "power_in"))
      (node (ref "U10") (pin "4") (pinfunction "GND_4") (pintype "power_in"))
      (node (ref "U2") (pin "21") (pinfunction "GND_21") (pintype "power_in"))
      (node (ref "U2") (pin "5") (pinfunction "GND_5") (pintype "power_in"))
      (node (ref "U3") (pin "11") (pinfunction "5A_11") (pintype "input"))
      (node (ref "U3") (pin "14") (pinfunction "6A_14") (pintype "input"))
      (node (ref "U3") (pin "8") (pinfunction "GND_8") (pintype "power_in"))
      (node (ref "U4") (pin "2") (pinfunction "GND_2") (pintype "power_in"))
      (node (ref "U5") (pin "8") (pinfunction "GND_8") (pintype "power_in"))
      (node (ref "U6") (pin "8") (pinfunction "GND_8") (pintype "power_in"))
      (node (ref "U7") (pin "18") (pinfunction "GND2_18") (pintype "power_in"))
      (node (ref "U7") (pin "21") (pinfunction "GND3_21") (pintype "power_in"))
      (node (ref "U7") (pin "25") (pinfunction "AGND_25") (pintype "power_in"))
      (node (ref "U7") (pin "26") (pinfunction "TEST_26") (pintype "input"))
      (node (ref "U7") (pin "7") (pinfunction "GND1_7") (pintype "power_in"))
      (node (ref "U8") (pin "10") (pinfunction "NC_7_10") (pintype "passive"))
      (node (ref "U8") (pin "11") (pinfunction "NC_8_11") (pintype "passive"))
      (node (ref "U8") (pin "12") (pinfunction "NC_12") (pintype "passive"))
      (node (ref "U8") (pin "13") (pinfunction "GND_13") (pintype "power_in"))
      (node (ref "U8") (pin "5") (pinfunction "NC_2_5") (pintype "passive"))
      (node (ref "U8") (pin "6") (pinfunction "NC_3_6") (pintype "passive"))
      (node (ref "U8") (pin "7") (pinfunction "NC_4_7") (pintype "passive"))
      (node (ref "U8") (pin "8") (pinfunction "NC_5_8") (pintype "passive"))
      (node (ref "U8") (pin "9") (pinfunction "NC_6_9") (pintype "passive"))
    )
    (net (code "29") (name "GREEN") (class "Default")
      (node (ref "JA2") (pin "N") (pinfunction "VIDEO_GREEN_N") (pintype "output"))
      (node (ref "JAMMA_IN") (pin "N") (pinfunction "GREEN_N") (pintype "input"))
      (node (ref "JAMMA_OUT_BTM") (pin "N") (pinfunction "VIDEO_GREEN_N") (pintype "output"))
      (node (ref "R15") (pin "1") (pinfunction "P$1_1") (pintype "passive"))
    )
    (net (code "30") (name "J") (class "Default")
      (node (ref "JA2") (pin "J") (pinfunction "COIN_CNT2_J") (pintype "bidirectional"))
      (node (ref "JAMMA_IN") (pin "J") (pinfunction "COINCNT-2_J") (pintype "bidirectional"))
      (node (ref "JAMMA_OUT_BTM") (pin "J") (pinfunction "COIN_CNT2_J") (pintype "bidirectional"))
    )
    (net (code "31") (name "JAMMA+5V") (class "Default")
      (node (ref "J+5V") (pin "TP") (pinfunction "TP_TP") (pintype "input"))
      (node (ref "JA1") (pin "3") (pinfunction "+5V_3") (pintype "power_in"))
      (node (ref "JA1") (pin "4") (pinfunction "+5V_4") (pintype "power_in"))
      (node (ref "JA2") (pin "C") (pinfunction "+5V_C") (pintype "power_in"))
      (node (ref "JA2") (pin "D") (pinfunction "+5V_D") (pintype "power_in"))
      (node (ref "JAMMA_IN") (pin "3") (pinfunction "+5V_3") (pintype "power_in"))
      (node (ref "JAMMA_IN") (pin "4") (pinfunction "+5V_4") (pintype "power_in"))
      (node (ref "JAMMA_IN") (pin "C") (pinfunction "+5V_C") (pintype "power_in"))
      (node (ref "JAMMA_IN") (pin "D") (pinfunction "+5V_D") (pintype "power_in"))
      (node (ref "JAMMA_OUT_BTM") (pin "C") (pinfunction "+5V_C") (pintype "power_in"))
      (node (ref "JAMMA_OUT_BTM") (pin "D") (pinfunction "+5V_D") (pintype "power_in"))
      (node (ref "JAMMA_OUT_TOP") (pin "3") (pinfunction "+5V_3") (pintype "power_in"))
      (node (ref "JAMMA_OUT_TOP") (pin "4") (pinfunction "+5V_4") (pintype "power_in"))
    )
    (net (code "32") (name "JAMMA+12V") (class "Default")
      (node (ref "D5") (pin "2") (pinfunction "P$2_2") (pintype "passive"))
      (node (ref "J+12V") (pin "TP") (pinfunction "TP_TP") (pintype "input"))
      (node (ref "JA1") (pin "6") (pinfunction "+12V_6") (pintype "power_in"))
      (node (ref "JA2") (pin "F") (pinfunction "+12V_F") (pintype "power_in"))
      (node (ref "JAMMA_IN") (pin "6") (pinfunction "+12V_6") (pintype "power_in"))
      (node (ref "JAMMA_IN") (pin "F") (pinfunction "+12V_F") (pintype "power_in"))
      (node (ref "JAMMA_OUT_BTM") (pin "F") (pinfunction "+12V_F") (pintype "power_in"))
      (node (ref "JAMMA_OUT_TOP") (pin "6") (pinfunction "+12V_6") (pintype "power_in"))
    )
    (net (code "33") (name "JAMMA-5V") (class "Default")
      (node (ref "JA1") (pin "5") (pinfunction "-5V_5") (pintype "power_in"))
      (node (ref "JA2") (pin "E") (pinfunction "-5V_E") (pintype "power_in"))
      (node (ref "JAMMA_IN") (pin "5") (pinfunction "-5V_5") (pintype "power_in"))
      (node (ref "JAMMA_IN") (pin "E") (pinfunction "-5V_E") (pintype "power_in"))
      (node (ref "JAMMA_OUT_BTM") (pin "E") (pinfunction "-5V_E") (pintype "power_in"))
      (node (ref "JAMMA_OUT_TOP") (pin "5") (pinfunction "-5V_5") (pintype "power_in"))
    )
    (net (code "34") (name "K") (class "Default")
      (node (ref "JA2") (pin "K") (pinfunction "COIN_LOC2_K") (pintype "bidirectional"))
      (node (ref "JAMMA_IN") (pin "K") (pinfunction "COIL-2_K") (pintype "bidirectional"))
      (node (ref "JAMMA_OUT_BTM") (pin "K") (pinfunction "COIN_LOC2_K") (pintype "bidirectional"))
    )
    (net (code "35") (name "Net-(C1-P$1)") (class "Default")
      (node (ref "C1") (pin "1") (pinfunction "P$1_1") (pintype "passive"))
      (node (ref "U2") (pin "7") (pinfunction "PB6_7") (pintype "bidirectional"))
      (node (ref "Y1") (pin "2") (pinfunction "2_2") (pintype "passive"))
    )
    (net (code "36") (name "Net-(C2-P$1)") (class "Default")
      (node (ref "C2") (pin "1") (pinfunction "P$1_1") (pintype "passive"))
      (node (ref "U2") (pin "8") (pinfunction "PB7_8") (pintype "bidirectional"))
      (node (ref "Y1") (pin "1") (pinfunction "1_1") (pintype "passive"))
    )
    (net (code "37") (name "Net-(C11-P$2)") (class "Default")
      (node (ref "C11") (pin "2") (pinfunction "P$2_2") (pintype "passive"))
      (node (ref "SJ1") (pin "1") (pinfunction "1_1") (pintype "passive"))
    )
    (net (code "38") (name "Net-(D1-P$1)") (class "Default")
      (node (ref "D1") (pin "+") (pinfunction "P$1_+") (pintype "passive"))
      (node (ref "U3") (pin "10") (pinfunction "4Y_10") (pintype "output"))
    )
    (net (code "39") (name "Net-(D1-P$2)") (class "Default")
      (node (ref "D1") (pin "-") (pinfunction "P$2_-") (pintype "passive"))
      (node (ref "R1") (pin "1") (pinfunction "P$1_1") (pintype "passive"))
    )
    (net (code "40") (name "Net-(D2-P$2)") (class "Default")
      (node (ref "D2") (pin "-") (pinfunction "P$2_-") (pintype "passive"))
      (node (ref "R3") (pin "1") (pinfunction "P$1_1") (pintype "passive"))
    )
    (net (code "41") (name "Net-(D3-RX-P$1)") (class "Default")
      (node (ref "D3-RX") (pin "+") (pinfunction "P$1_+") (pintype "passive"))
      (node (ref "R4") (pin "1") (pinfunction "P$1_1") (pintype "passive"))
    )
    (net (code "42") (name "Net-(D3-RX-P$2)") (class "Default")
      (node (ref "D3-RX") (pin "-") (pinfunction "P$2_-") (pintype "passive"))
      (node (ref "U7") (pin "22") (pinfunction "RXLED_22") (pintype "bidirectional"))
    )
    (net (code "43") (name "Net-(D4-TX-P$1)") (class "Default")
      (node (ref "D4-TX") (pin "+") (pinfunction "P$1_+") (pintype "passive"))
      (node (ref "R5") (pin "1") (pinfunction "P$1_1") (pintype "passive"))
    )
    (net (code "44") (name "Net-(D4-TX-P$2)") (class "Default")
      (node (ref "D4-TX") (pin "-") (pinfunction "P$2_-") (pintype "passive"))
      (node (ref "U7") (pin "23") (pinfunction "TXLED_23") (pintype "bidirectional"))
    )
    (net (code "45") (name "Net-(J1-Pad2)") (class "Default")
      (node (ref "J1") (pin "2") (pinfunction "2_2") (pintype "passive"))
      (node (ref "T1") (pin "4") (pinfunction "4_4") (pintype "passive"))
    )
    (net (code "46") (name "Net-(J1-Pad3)") (class "Default")
      (node (ref "J1") (pin "3") (pinfunction "3_3") (pintype "passive"))
      (node (ref "T2") (pin "4") (pinfunction "4_4") (pintype "passive"))
    )
    (net (code "47") (name "Net-(J3-+)") (class "Default")
      (node (ref "J3") (pin "1") (pinfunction "+_1") (pintype "bidirectional"))
      (node (ref "U8") (pin "14") (pinfunction "VBAT_14") (pintype "power_in"))
    )
    (net (code "48") (name "Net-(J4-CD{slash}DAT3)") (class "Default")
      (node (ref "J4") (pin "2") (pinfunction "CD/DAT3_2") (pintype "bidirectional"))
      (node (ref "R1") (pin "2") (pinfunction "P$2_2") (pintype "passive"))
      (node (ref "U3") (pin "6") (pinfunction "3Y_6") (pintype "output"))
    )
    (net (code "49") (name "Net-(J4-CLK)") (class "Default")
      (node (ref "J4") (pin "5") (pinfunction "CLK_5") (pintype "bidirectional"))
      (node (ref "U3") (pin "4") (pinfunction "2Y_4") (pintype "output"))
    )
    (net (code "50") (name "Net-(J4-CMD)") (class "Default")
      (node (ref "J4") (pin "3") (pinfunction "CMD_3") (pintype "bidirectional"))
      (node (ref "U3") (pin "2") (pinfunction "1Y_2") (pintype "output"))
    )
    (net (code "51") (name "Net-(R10-P$1)") (class "Default")
      (node (ref "R10") (pin "1") (pinfunction "P$1_1") (pintype "passive"))
      (node (ref "S2") (pin "2") (pinfunction "2_2") (pintype "passive"))
    )
    (net (code "52") (name "Net-(R10-P$2)") (class "Default")
      (node (ref "R10") (pin "2") (pinfunction "P$2_2") (pintype "passive"))
      (node (ref "R13") (pin "2") (pinfunction "P$2_2") (pintype "passive"))
      (node (ref "T2") (pin "1") (pinfunction "1_1") (pintype "passive"))
    )
    (net (code "53") (name "Net-(R11-P$2)") (class "Default")
      (node (ref "R11") (pin "2") (pinfunction "P$2_2") (pintype "passive"))
      (node (ref "R12") (pin "2") (pinfunction "P$2_2") (pintype "passive"))
      (node (ref "T1") (pin "1") (pinfunction "1_1") (pintype "passive"))
    )
    (net (code "54") (name "Net-(R12-P$1)") (class "Default")
      (node (ref "R12") (pin "1") (pinfunction "P$1_1") (pintype "passive"))
      (node (ref "R13") (pin "1") (pinfunction "P$1_1") (pintype "passive"))
      (node (ref "S2") (pin "5") (pinfunction "5_5") (pintype "passive"))
      (node (ref "T1") (pin "3") (pinfunction "3_3") (pintype "passive"))
      (node (ref "T2") (pin "3") (pinfunction "3_3") (pintype "passive"))
    )
    (net (code "55") (name "Net-(R14-P$2)") (class "Default")
      (node (ref "R14") (pin "2") (pinfunction "P$2_2") (pintype "passive"))
      (node (ref "VGA_OUT") (pin "1") (pinfunction "1_1") (pintype "passive"))
    )
    (net (code "56") (name "Net-(R15-P$2)") (class "Default")
      (node (ref "R15") (pin "2") (pinfunction "P$2_2") (pintype "passive"))
      (node (ref "VGA_OUT") (pin "2") (pinfunction "2_2") (pintype "passive"))
    )
    (net (code "57") (name "Net-(R16-P$2)") (class "Default")
      (node (ref "R16") (pin "2") (pinfunction "P$2_2") (pintype "passive"))
      (node (ref "VGA_OUT") (pin "3") (pinfunction "3_3") (pintype "passive"))
    )
    (net (code "58") (name "Net-(SYNC_POT-WIPER)") (class "Default")
      (node (ref "SYNC_POT") (pin "2") (pinfunction "WIPER_2") (pintype "passive"))
      (node (ref "VGA_OUT") (pin "13") (pinfunction "13_13") (pintype "passive"))
    )
    (net (code "59") (name "Net-(U1-DS)") (class "Default")
      (node (ref "U1") (pin "10") (pinfunction "DS_10") (pintype "input"))
      (node (ref "U5") (pin "9") (pinfunction "Q7_9") (pintype "output"))
    )
    (net (code "60") (name "Net-(U5-DS)") (class "Default")
      (node (ref "U5") (pin "10") (pinfunction "DS_10") (pintype "input"))
      (node (ref "U6") (pin "9") (pinfunction "Q7_9") (pintype "output"))
    )
    (net (code "61") (name "Net-(U10-1OUT)") (class "Default")
      (node (ref "U10") (pin "1") (pinfunction "1OUT_1") (pintype "output"))
      (node (ref "U10") (pin "5") (pinfunction "2IN+_5") (pintype "input"))
    )
    (net (code "62") (name "P") (class "Default")
      (node (ref "JA2") (pin "P") (pinfunction "VIDEO_SYNC_P") (pintype "output"))
      (node (ref "JAMMA_IN") (pin "P") (pinfunction "SYNC_P") (pintype "input"))
      (node (ref "JAMMA_OUT_BTM") (pin "P") (pinfunction "VIDEO_SYNC_P") (pintype "output"))
      (node (ref "SYNC_POT") (pin "1") (pinfunction "CCW_1") (pintype "passive"))
    )
    (net (code "63") (name "PD4") (class "Default")
      (node (ref "U1") (pin "1") (pinfunction "~{PL}_1") (pintype "input"))
      (node (ref "U2") (pin "2") (pinfunction "PD4_2") (pintype "bidirectional"))
      (node (ref "U5") (pin "1") (pinfunction "~{PL}_1") (pintype "input"))
      (node (ref "U6") (pin "1") (pinfunction "~{PL}_1") (pintype "input"))
    )
    (net (code "64") (name "PD5") (class "Default")
      (node (ref "U1") (pin "15") (pinfunction "~{CE}_15") (pintype "input"))
      (node (ref "U2") (pin "9") (pinfunction "PD5_9") (pintype "bidirectional"))
      (node (ref "U5") (pin "15") (pinfunction "~{CE}_15") (pintype "input"))
      (node (ref "U6") (pin "15") (pinfunction "~{CE}_15") (pintype "input"))
    )
    (net (code "65") (name "PD6") (class "Default")
      (node (ref "U1") (pin "9") (pinfunction "Q7_9") (pintype "output"))
      (node (ref "U2") (pin "10") (pinfunction "PD6_10") (pintype "bidirectional"))
    )
    (net (code "66") (name "PD7") (class "Default")
      (node (ref "U1") (pin "2") (pinfunction "CP_2") (pintype "input"))
      (node (ref "U2") (pin "11") (pinfunction "PD7_11") (pintype "bidirectional"))
      (node (ref "U5") (pin "2") (pinfunction "CP_2") (pintype "input"))
      (node (ref "U6") (pin "2") (pinfunction "CP_2") (pintype "input"))
    )
    (net (code "67") (name "R") (class "Default")
      (node (ref "JA2") (pin "R") (pinfunction "SERVICE_SW_R") (pintype "input"))
      (node (ref "JAMMA_IN") (pin "R") (pinfunction "SERVICE_R") (pintype "output"))
      (node (ref "JAMMA_OUT_BTM") (pin "R") (pinfunction "SERVICE_SW_R") (pintype "input"))
      (node (ref "U6") (pin "3") (pinfunction "D4_3") (pintype "input"))
    )
    (net (code "68") (name "RED") (class "Default")
      (node (ref "JA1") (pin "12") (pinfunction "VIDEO_RED_12") (pintype "output"))
      (node (ref "JAMMA_IN") (pin "12") (pinfunction "RED_12") (pintype "input"))
      (node (ref "JAMMA_OUT_TOP") (pin "12") (pinfunction "VIDEO_RED_12") (pintype "output"))
      (node (ref "R14") (pin "1") (pinfunction "P$1_1") (pintype "passive"))
    )
    (net (code "69") (name "RESET") (class "Default")
      (node (ref "J2") (pin "5") (pinfunction "5_5") (pintype "bidirectional"))
      (node (ref "R2") (pin "2") (pinfunction "P$2_2") (pintype "passive"))
      (node (ref "S1") (pin "3") (pinfunction "3_3") (pintype "passive"))
      (node (ref "S1") (pin "4") (pinfunction "4_4") (pintype "passive"))
      (node (ref "SJ1") (pin "2") (pinfunction "2_2") (pintype "passive"))
      (node (ref "U2") (pin "29") (pinfunction "PC6/~{RESET}_29") (pintype "bidirectional"))
    )
    (net (code "70") (name "RTC_SQW") (class "Default")
      (node (ref "R17") (pin "2") (pinfunction "P$2_2") (pintype "passive"))
      (node (ref "U2") (pin "26") (pinfunction "PC3_26") (pintype "bidirectional"))
      (node (ref "U8") (pin "3") (pinfunction "~{INT/SQW}_3") (pintype "passive"))
    )
    (net (code "71") (name "RTS") (class "Default")
      (node (ref "JP1") (pin "3") (pinfunction "3_3") (pintype "passive"))
      (node (ref "U7") (pin "3") (pinfunction "RTS_3") (pintype "bidirectional"))
    )
    (net (code "72") (name "S") (class "Default")
      (node (ref "JA2") (pin "S") (pinfunction "TILT_SW_S") (pintype "input"))
      (node (ref "JAMMA_IN") (pin "S") (pinfunction "TILT_S") (pintype "output"))
      (node (ref "JAMMA_OUT_BTM") (pin "S") (pinfunction "TILT_SW_S") (pintype "input"))
    )
    (net (code "73") (name "SCL") (class "Default")
      (node (ref "R6") (pin "2") (pinfunction "P$2_2") (pintype "passive"))
      (node (ref "U2") (pin "28") (pinfunction "PC5_28") (pintype "bidirectional"))
      (node (ref "U8") (pin "16") (pinfunction "SCL_16") (pintype "passive"))
    )
    (net (code "74") (name "SDA") (class "Default")
      (node (ref "R7") (pin "2") (pinfunction "P$2_2") (pintype "passive"))
      (node (ref "U2") (pin "27") (pinfunction "PC4_27") (pintype "bidirectional"))
      (node (ref "U8") (pin "15") (pinfunction "SDA_15") (pintype "passive"))
    )
    (net (code "75") (name "SPK+") (class "Default")
      (node (ref "JA1") (pin "10") (pinfunction "SPK+_10") (pintype "output"))
      (node (ref "JAMMA_IN") (pin "10") (pinfunction "SPEAK+_10") (pintype "bidirectional"))
      (node (ref "JAMMA_OUT_TOP") (pin "10") (pinfunction "SPK+_10") (pintype "output"))
      (node (ref "R11") (pin "1") (pinfunction "P$1_1") (pintype "passive"))
      (node (ref "S2") (pin "1") (pinfunction "1_1") (pintype "passive"))
    )
    (net (code "76") (name "SPK-") (class "Default")
      (node (ref "JA2") (pin "L") (pinfunction "SPK-_L") (pintype "output"))
      (node (ref "JAMMA_IN") (pin "L") (pinfunction "SPEAK-_L") (pintype "bidirectional"))
      (node (ref "JAMMA_OUT_BTM") (pin "L") (pinfunction "SPK-_L") (pintype "output"))
      (node (ref "S2") (pin "3") (pinfunction "3_3") (pintype "passive"))
      (node (ref "S2") (pin "4") (pinfunction "4_4") (pintype "passive"))
    )
    (net (code "77") (name "T") (class "Default")
      (node (ref "JA2") (pin "T") (pinfunction "COIN_SW2_T") (pintype "input"))
      (node (ref "JAMMA_IN") (pin "T") (pinfunction "COIN-2_T") (pintype "output"))
      (node (ref "JAMMA_OUT_BTM") (pin "T") (pinfunction "COIN_SW2_T") (pintype "input"))
      (node (ref "U6") (pin "4") (pinfunction "D5_4") (pintype "input"))
    )
    (net (code "78") (name "U") (class "Default")
      (node (ref "JA2") (pin "U") (pinfunction "START_SW2_U") (pintype "input"))
      (node (ref "JAMMA_IN") (pin "U") (pinfunction "2P-START_U") (pintype "output"))
      (node (ref "JAMMA_OUT_BTM") (pin "U") (pinfunction "START_SW2_U") (pintype "input"))
      (node (ref "U6") (pin "5") (pinfunction "D6_5") (pintype "input"))
    )
    (net (code "79") (name "USBVCC") (class "Default")
      (node (ref "C10") (pin "1") (pinfunction "P$1_1") (pintype "passive"))
      (node (ref "C9") (pin "1") (pinfunction "P$1_1") (pintype "passive"))
      (node (ref "F1") (pin "2") (pinfunction "P$2_2") (pintype "passive"))
      (node (ref "R4") (pin "2") (pinfunction "P$2_2") (pintype "passive"))
      (node (ref "R5") (pin "2") (pinfunction "P$2_2") (pintype "passive"))
      (node (ref "U7") (pin "20") (pinfunction "VCC_20") (pintype "power_in"))
      (node (ref "U7") (pin "4") (pinfunction "VCCIO_4") (pintype "power_in"))
      (node (ref "U9") (pin "4") (pinfunction "D_4") (pintype "passive"))
      (node (ref "USBVCC") (pin "TP") (pinfunction "TP_TP") (pintype "input"))
    )
    (net (code "80") (name "USB_V") (class "Default")
      (node (ref "F1") (pin "1") (pinfunction "P$1_1") (pintype "passive"))
      (node (ref "J6") (pin "1") (pinfunction "VBUS_1") (pintype "power_in"))
    )
    (net (code "81") (name "V") (class "Default")
      (node (ref "JA2") (pin "V") (pinfunction "2P1_UP_V") (pintype "input"))
      (node (ref "JAMMA_IN") (pin "V") (pinfunction "2P-UP_V") (pintype "output"))
      (node (ref "JAMMA_OUT_BTM") (pin "V") (pinfunction "2P1_UP_V") (pintype "input"))
      (node (ref "U6") (pin "6") (pinfunction "D7_6") (pintype "input"))
    )
    (net (code "82") (name "VCC") (class "Default")
      (node (ref "+5V") (pin "TP") (pinfunction "TP_TP") (pintype "input"))
      (node (ref "C13") (pin "1") (pinfunction "P$1_1") (pintype "passive"))
      (node (ref "C14") (pin "1") (pinfunction "P$1_1") (pintype "passive"))
      (node (ref "C3") (pin "2") (pinfunction "P$2_2") (pintype "passive"))
      (node (ref "C6") (pin "1") (pinfunction "P$1_1") (pintype "passive"))
      (node (ref "C8") (pin "1") (pinfunction "P$1_1") (pintype "passive"))
      (node (ref "D2") (pin "+") (pinfunction "P$1_+") (pintype "passive"))
      (node (ref "IC1") (pin "2") (pinfunction "VO_2") (pintype "passive"))
      (node (ref "J2") (pin "2") (pinfunction "2_2") (pintype "bidirectional"))
      (node (ref "R17") (pin "1") (pinfunction "P$1_1") (pintype "passive"))
      (node (ref "R2") (pin "1") (pinfunction "P$1_1") (pintype "passive"))
      (node (ref "R6") (pin "1") (pinfunction "P$1_1") (pintype "passive"))
      (node (ref "R7") (pin "1") (pinfunction "P$1_1") (pintype "passive"))
      (node (ref "U1") (pin "16") (pinfunction "VCC_16") (pintype "power_in"))
      (node (ref "U10") (pin "8") (pinfunction "VCC_8") (pintype "power_in"))
      (node (ref "U2") (pin "18") (pinfunction "AVCC_18") (pintype "power_in"))
      (node (ref "U2") (pin "4") (pinfunction "VCC_4") (pintype "power_in"))
      (node (ref "U4") (pin "1") (pinfunction "VIN_1") (pintype "input"))
      (node (ref "U4") (pin "3") (pinfunction "ON/~{OFF}_3") (pintype "passive"))
      (node (ref "U5") (pin "16") (pinfunction "VCC_16") (pintype "power_in"))
      (node (ref "U6") (pin "16") (pinfunction "VCC_16") (pintype "power_in"))
      (node (ref "U8") (pin "2") (pinfunction "VCC_2") (pintype "power_in"))
      (node (ref "U9") (pin "3") (pinfunction "S_3") (pintype "passive"))
    )
    (net (code "83") (name "VCC33") (class "Default")
      (node (ref "C7") (pin "2") (pinfunction "P$2_2") (pintype "passive"))
      (node (ref "U10") (pin "2") (pinfunction "1IN-_2") (pintype "input"))
      (node (ref "U7") (pin "17") (pinfunction "3V3OUT_17") (pintype "output"))
    )
    (net (code "84") (name "VCC_2") (class "Default")
      (node (ref "+3.3V") (pin "TP") (pinfunction "TP_TP") (pintype "input"))
      (node (ref "C4") (pin "2") (pinfunction "P$2_2") (pintype "passive"))
      (node (ref "J4") (pin "4") (pinfunction "VDD_4") (pintype "bidirectional"))
      (node (ref "U3") (pin "1") (pinfunction "VCC_1") (pintype "power_in"))
      (node (ref "U4") (pin "5") (pinfunction "VOUT_5") (pintype "output"))
    )
    (net (code "85") (name "VGROUND") (class "Default")
      (node (ref "JA1") (pin "14") (pinfunction "VIDEO_GND_14") (pintype "output"))
      (node (ref "JAMMA_IN") (pin "14") (pinfunction "GROUND_14") (pintype "input"))
      (node (ref "JAMMA_OUT_TOP") (pin "14") (pinfunction "VIDEO_GND_14") (pintype "output"))
      (node (ref "VGA_OUT") (pin "10") (pinfunction "10_10") (pintype "passive"))
      (node (ref "VGA_OUT") (pin "5") (pinfunction "5_5") (pintype "passive"))
      (node (ref "VGA_OUT") (pin "6") (pinfunction "6_6") (pintype "passive"))
      (node (ref "VGA_OUT") (pin "7") (pinfunction "7_7") (pintype "passive"))
      (node (ref "VGA_OUT") (pin "8") (pinfunction "8_8") (pintype "passive"))
    )
    (net (code "86") (name "VIN") (class "Default")
      (node (ref "C5") (pin "1") (pinfunction "P$1_1") (pintype "passive"))
      (node (ref "D5") (pin "1") (pinfunction "P$1_1") (pintype "passive"))
      (node (ref "IC1") (pin "1") (pinfunction "VI_1") (pintype "input"))
      (node (ref "R8") (pin "2") (pinfunction "P$2_2") (pintype "passive"))
    )
    (net (code "87") (name "W") (class "Default")
      (node (ref "JA2") (pin "W") (pinfunction "2P2_DOWN_W") (pintype "input"))
      (node (ref "JAMMA_IN") (pin "W") (pinfunction "2P-DOWN_W") (pintype "output"))
      (node (ref "JAMMA_OUT_BTM") (pin "W") (pinfunction "2P2_DOWN_W") (pintype "input"))
      (node (ref "U5") (pin "3") (pinfunction "D4_3") (pintype "input"))
    )
    (net (code "88") (name "X") (class "Default")
      (node (ref "JA2") (pin "X") (pinfunction "2P3_LEFT_X") (pintype "input"))
      (node (ref "JAMMA_IN") (pin "X") (pinfunction "2P-LEFT_X") (pintype "output"))
      (node (ref "JAMMA_OUT_BTM") (pin "X") (pinfunction "2P3_LEFT_X") (pintype "input"))
      (node (ref "U5") (pin "4") (pinfunction "D5_4") (pintype "input"))
    )
    (net (code "89") (name "Y") (class "Default")
      (node (ref "JA2") (pin "Y") (pinfunction "2P4_RIGHT_Y") (pintype "input"))
      (node (ref "JAMMA_IN") (pin "Y") (pinfunction "2P-RIGHT_Y") (pintype "output"))
      (node (ref "JAMMA_OUT_BTM") (pin "Y") (pinfunction "2P4_RIGHT_Y") (pintype "input"))
      (node (ref "U5") (pin "5") (pinfunction "D6_5") (pintype "input"))
    )
    (net (code "90") (name "Z") (class "Default")
      (node (ref "JA2") (pin "Z") (pinfunction "2P5_PUSH1_Z") (pintype "input"))
      (node (ref "JAMMA_IN") (pin "Z") (pinfunction "2P-BTN1_Z") (pintype "output"))
      (node (ref "JAMMA_OUT_BTM") (pin "Z") (pinfunction "2P5_PUSH1_Z") (pintype "input"))
      (node (ref "U5") (pin "6") (pinfunction "D7_6") (pintype "input"))
    )
    (net (code "91") (name "_A") (class "Default")
      (node (ref "JA2") (pin "_A") (pinfunction "2P6_PUSH2__A") (pintype "input"))
      (node (ref "JAMMA_IN") (pin "_A") (pinfunction "2P-BTN2__A") (pintype "output"))
      (node (ref "JAMMA_OUT_BTM") (pin "_A") (pinfunction "2P6_PUSH2__A") (pintype "input"))
      (node (ref "U1") (pin "3") (pinfunction "D4_3") (pintype "input"))
    )
    (net (code "92") (name "_B") (class "Default")
      (node (ref "JA2") (pin "_B") (pinfunction "2P7_PUSH3__B") (pintype "input"))
      (node (ref "JAMMA_IN") (pin "_B") (pinfunction "2P-BTN3__B") (pintype "output"))
      (node (ref "JAMMA_OUT_BTM") (pin "_B") (pinfunction "2P7_PUSH3__B") (pintype "input"))
      (node (ref "U1") (pin "4") (pinfunction "D5_4") (pintype "input"))
    )
    (net (code "93") (name "_C") (class "Default")
      (node (ref "JA2") (pin "_C") (pinfunction "2P8__C") (pintype "input"))
      (node (ref "JAMMA_IN") (pin "_C") (pinfunction "_C__C") (pintype "output"))
      (node (ref "JAMMA_OUT_BTM") (pin "_C") (pinfunction "2P8__C") (pintype "input"))
      (node (ref "U1") (pin "5") (pinfunction "D6_5") (pintype "input"))
    )
    (net (code "94") (name "_D") (class "Default")
      (node (ref "JA2") (pin "_D") (pinfunction "2P9__D") (pintype "input"))
      (node (ref "JAMMA_IN") (pin "_D") (pinfunction "_D__D") (pintype "output"))
      (node (ref "JAMMA_OUT_BTM") (pin "_D") (pinfunction "2P9__D") (pintype "input"))
      (node (ref "U1") (pin "6") (pinfunction "D7_6") (pintype "input"))
    )
    (net (code "95") (name "unconnected-(J4-CDW(A)-Pad9)") (class "Default")
      (node (ref "J4") (pin "9") (pinfunction "CDW(A)_9") (pintype "bidirectional"))
    )
    (net (code "96") (name "unconnected-(J4-CDW(B)-Pad10)") (class "Default")
      (node (ref "J4") (pin "10") (pinfunction "CDW(B)_10") (pintype "bidirectional"))
    )
    (net (code "97") (name "unconnected-(JA2-AUDIO_GND-PadM)") (class "Default")
      (node (ref "JA2") (pin "M") (pinfunction "AUDIO_GND_M") (pintype "output"))
    )
    (net (code "98") (name "unconnected-(JAMMA_IN-KEY-Pad7)") (class "Default")
      (node (ref "JAMMA_IN") (pin "7") (pinfunction "KEY_7") (pintype "no_connect"))
    )
    (net (code "99") (name "unconnected-(JAMMA_IN-KEY-PadH)") (class "Default")
      (node (ref "JAMMA_IN") (pin "H") (pinfunction "KEY_H") (pintype "no_connect"))
    )
    (net (code "100") (name "unconnected-(JAMMA_IN-Pad11)") (class "Default")
      (node (ref "JAMMA_IN") (pin "11") (pinfunction "11_11") (pintype "no_connect"))
    )
    (net (code "101") (name "unconnected-(JAMMA_IN-PadM)") (class "Default")
      (node (ref "JAMMA_IN") (pin "M") (pinfunction "M_M") (pintype "no_connect"))
    )
    (net (code "102") (name "unconnected-(JAMMA_OUT_BTM-AUDIO_GND-PadM)") (class "Default")
      (node (ref "JAMMA_OUT_BTM") (pin "M") (pinfunction "AUDIO_GND_M") (pintype "output"))
    )
    (net (code "103") (name "unconnected-(JAMMA_OUT_TOP-AUDIO+-Pad11)") (class "Default")
      (node (ref "JAMMA_OUT_TOP") (pin "11") (pinfunction "AUDIO+_11") (pintype "output"))
    )
    (net (code "104") (name "unconnected-(SYNC_POT-CW-Pad3)") (class "Default")
      (node (ref "SYNC_POT") (pin "3") (pinfunction "CW_3") (pintype "passive"))
    )
    (net (code "105") (name "unconnected-(T1-Pad2)") (class "Default")
      (node (ref "T1") (pin "2") (pinfunction "2_2") (pintype "passive"))
    )
    (net (code "106") (name "unconnected-(T1-Pad5)") (class "Default")
      (node (ref "T1") (pin "5") (pinfunction "5_5") (pintype "passive"))
    )
    (net (code "107") (name "unconnected-(T2-Pad2)") (class "Default")
      (node (ref "T2") (pin "2") (pinfunction "2_2") (pintype "passive"))
    )
    (net (code "108") (name "unconnected-(T2-Pad5)") (class "Default")
      (node (ref "T2") (pin "5") (pinfunction "5_5") (pintype "passive"))
    )
    (net (code "109") (name "unconnected-(U1-~{Q7}-Pad7)") (class "Default")
      (node (ref "U1") (pin "7") (pinfunction "~{Q7}_7") (pintype "output"))
    )
    (net (code "110") (name "unconnected-(U2-AREF-Pad20)") (class "Default")
      (node (ref "U2") (pin "20") (pinfunction "AREF_20") (pintype "input"))
    )
    (net (code "111") (name "unconnected-(U2-PB0-Pad12)") (class "Default")
      (node (ref "U2") (pin "12") (pinfunction "PB0_12") (pintype "bidirectional"))
    )
    (net (code "112") (name "unconnected-(U2-PB1-Pad13)") (class "Default")
      (node (ref "U2") (pin "13") (pinfunction "PB1_13") (pintype "bidirectional"))
    )
    (net (code "113") (name "unconnected-(U2-PC0-Pad23)") (class "Default")
      (node (ref "U2") (pin "23") (pinfunction "PC0_23") (pintype "bidirectional"))
    )
    (net (code "114") (name "unconnected-(U2-PC1-Pad24)") (class "Default")
      (node (ref "U2") (pin "24") (pinfunction "PC1_24") (pintype "bidirectional"))
    )
    (net (code "115") (name "unconnected-(U2-PC2-Pad25)") (class "Default")
      (node (ref "U2") (pin "25") (pinfunction "PC2_25") (pintype "bidirectional"))
    )
    (net (code "116") (name "unconnected-(U2-PD2-Pad32)") (class "Default")
      (node (ref "U2") (pin "32") (pinfunction "PD2_32") (pintype "bidirectional"))
    )
    (net (code "117") (name "unconnected-(U2-PD3-Pad1)") (class "Default")
      (node (ref "U2") (pin "1") (pinfunction "PD3_1") (pintype "bidirectional"))
    )
    (net (code "118") (name "unconnected-(U2-PE0-Pad3)") (class "Default")
      (node (ref "U2") (pin "3") (pinfunction "PE0_3") (pintype "bidirectional"))
    )
    (net (code "119") (name "unconnected-(U2-PE1-Pad6)") (class "Default")
      (node (ref "U2") (pin "6") (pinfunction "PE1_6") (pintype "bidirectional"))
    )
    (net (code "120") (name "unconnected-(U2-PE2-Pad19)") (class "Default")
      (node (ref "U2") (pin "19") (pinfunction "PE2_19") (pintype "bidirectional"))
    )
    (net (code "121") (name "unconnected-(U2-PE3-Pad22)") (class "Default")
      (node (ref "U2") (pin "22") (pinfunction "PE3_22") (pintype "bidirectional"))
    )
    (net (code "122") (name "unconnected-(U3-5Y-Pad12)") (class "Default")
      (node (ref "U3") (pin "12") (pinfunction "5Y_12") (pintype "output"))
    )
    (net (code "123") (name "unconnected-(U3-6Y-Pad15)") (class "Default")
      (node (ref "U3") (pin "15") (pinfunction "6Y_15") (pintype "output"))
    )
    (net (code "124") (name "unconnected-(U3-NC-Pad13)") (class "Default")
      (node (ref "U3") (pin "13") (pinfunction "NC_13") (pintype "no_connect"))
    )
    (net (code "125") (name "unconnected-(U3-NC-Pad16)") (class "Default")
      (node (ref "U3") (pin "16") (pinfunction "NC_16") (pintype "no_connect"))
    )
    (net (code "126") (name "unconnected-(U4-NC-Pad4)") (class "Default")
      (node (ref "U4") (pin "4") (pinfunction "NC_4") (pintype "passive"))
    )
    (net (code "127") (name "unconnected-(U5-~{Q7}-Pad7)") (class "Default")
      (node (ref "U5") (pin "7") (pinfunction "~{Q7}_7") (pintype "output"))
    )
    (net (code "128") (name "unconnected-(U6-DS-Pad10)") (class "Default")
      (node (ref "U6") (pin "10") (pinfunction "DS_10") (pintype "input"))
    )
    (net (code "129") (name "unconnected-(U6-~{Q7}-Pad7)") (class "Default")
      (node (ref "U6") (pin "7") (pinfunction "~{Q7}_7") (pintype "output"))
    )
    (net (code "130") (name "unconnected-(U7-CTS-Pad11)") (class "Default")
      (node (ref "U7") (pin "11") (pinfunction "CTS_11") (pintype "bidirectional"))
    )
    (net (code "131") (name "unconnected-(U8-32KHZ-Pad1)") (class "Default")
      (node (ref "U8") (pin "1") (pinfunction "32KHZ_1") (pintype "passive"))
    )
    (net (code "132") (name "unconnected-(U8-~{RST}-Pad4)") (class "Default")
      (node (ref "U8") (pin "4") (pinfunction "~{RST}_4") (pintype "passive"))
    )
    (net (code "133") (name "unconnected-(U9-D_2-Pad2)") (class "Default")
      (node (ref "U9") (pin "2") (pinfunction "D_2_2") (pintype "passive"))
    )
    (net (code "134") (name "unconnected-(VGA_OUT-Pad4)") (class "Default")
      (node (ref "VGA_OUT") (pin "4") (pinfunction "4_4") (pintype "passive"))
    )
    (net (code "135") (name "unconnected-(VGA_OUT-Pad9)") (class "Default")
      (node (ref "VGA_OUT") (pin "9") (pinfunction "9_9") (pintype "passive"))
    )
    (net (code "136") (name "unconnected-(VGA_OUT-Pad11)") (class "Default")
      (node (ref "VGA_OUT") (pin "11") (pinfunction "11_11") (pintype "passive"))
    )
    (net (code "137") (name "unconnected-(VGA_OUT-Pad12)") (class "Default")
      (node (ref "VGA_OUT") (pin "12") (pinfunction "12_12") (pintype "passive"))
    )
    (net (code "138") (name "unconnected-(VGA_OUT-Pad14)") (class "Default")
      (node (ref "VGA_OUT") (pin "14") (pinfunction "14_14") (pintype "passive"))
    )
    (net (code "139") (name "unconnected-(VGA_OUT-Pad15)") (class "Default")
      (node (ref "VGA_OUT") (pin "15") (pinfunction "15_15") (pintype "passive"))
    )
  )
)
